# processingController.net
KiCad netlist of a schematic drawn in EAGLE
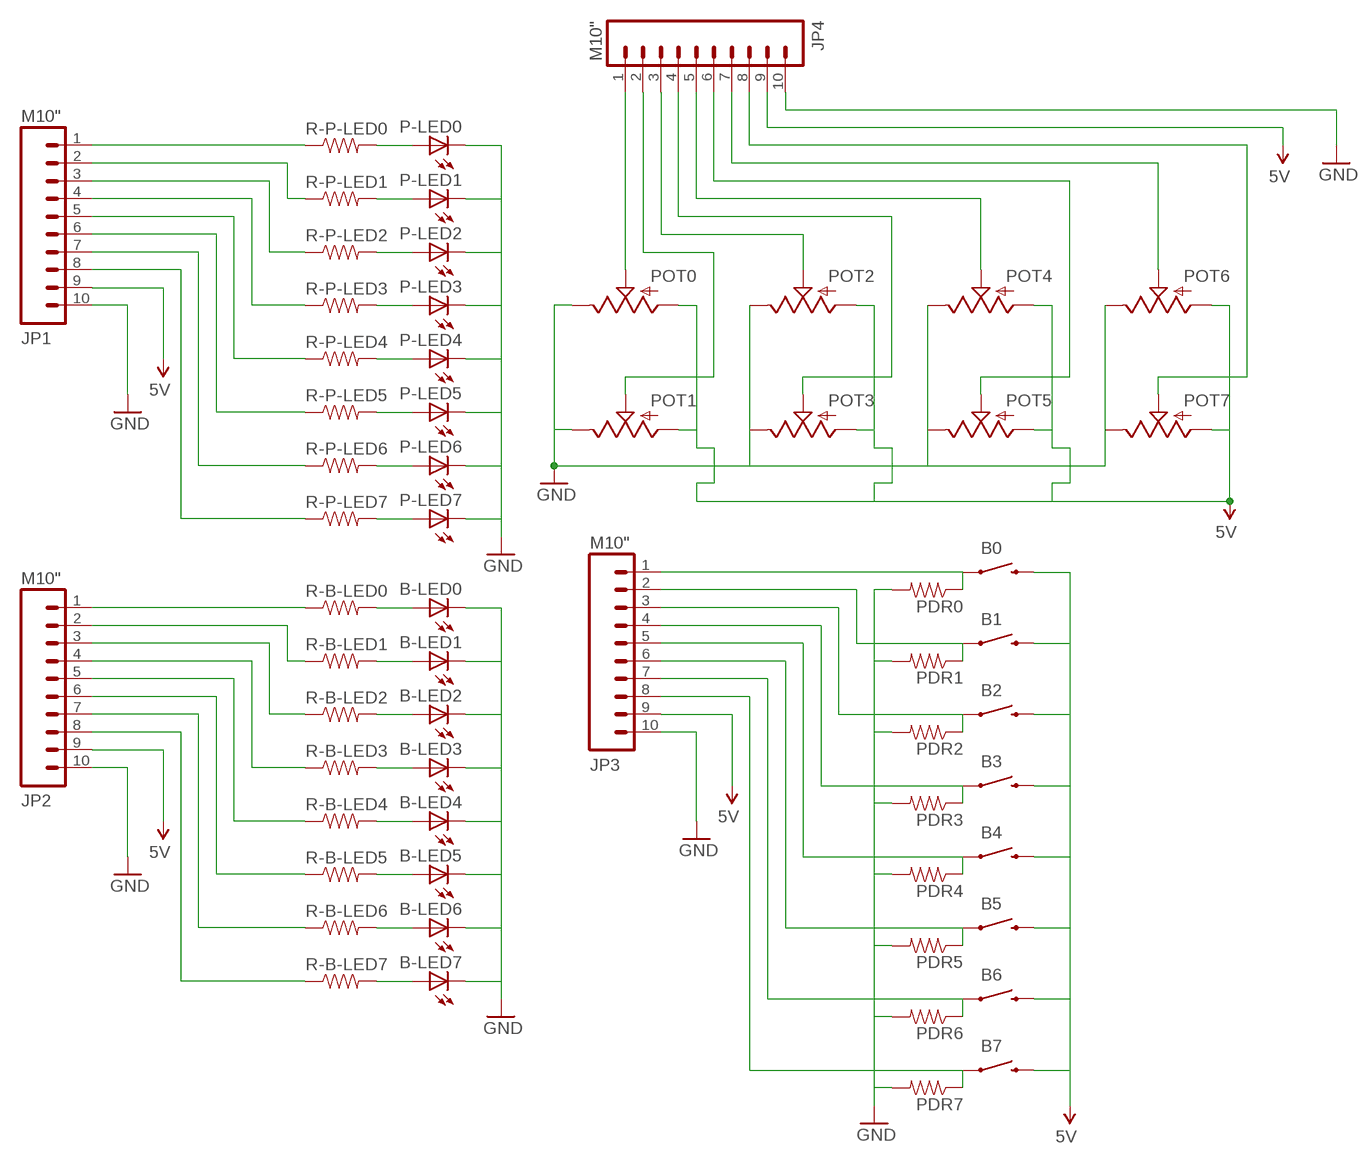
[diagram p0: schematic, sheet 1]

(export (version "E")
  (design (tool "Eeschema 10.0.6"))
  (components
    (comp (ref "B-LED0")
      (value "LED3MM")
      (footprint "eagle-import:LED3MM")
      (libsource (lib "eagle-import") (part "LED3MM"))
    )
    (comp (ref "B-LED1")
      (value "LED3MM")
      (footprint "eagle-import:LED3MM")
      (libsource (lib "eagle-import") (part "LED3MM"))
    )
    (comp (ref "B-LED2")
      (value "LED3MM")
      (footprint "eagle-import:LED3MM")
      (libsource (lib "eagle-import") (part "LED3MM"))
    )
    (comp (ref "B-LED3")
      (value "LED3MM")
      (footprint "eagle-import:LED3MM")
      (libsource (lib "eagle-import") (part "LED3MM"))
    )
    (comp (ref "B-LED4")
      (value "LED3MM")
      (footprint "eagle-import:LED3MM")
      (libsource (lib "eagle-import") (part "LED3MM"))
    )
    (comp (ref "B-LED5")
      (value "LED3MM")
      (footprint "eagle-import:LED3MM")
      (libsource (lib "eagle-import") (part "LED3MM"))
    )
    (comp (ref "B-LED6")
      (value "LED3MM")
      (footprint "eagle-import:LED3MM")
      (libsource (lib "eagle-import") (part "LED3MM"))
    )
    (comp (ref "B-LED7")
      (value "LED3MM")
      (footprint "eagle-import:LED3MM")
      (libsource (lib "eagle-import") (part "LED3MM"))
    )
    (comp (ref "B0")
      (value "SWITCH-MOMENTARY-212MM")
      (footprint "eagle-import:TACTILE-PTH-12MM")
      (libsource (lib "eagle-import") (part "SWITCH-MOMENTARY-212MM"))
    )
    (comp (ref "B1")
      (value "SWITCH-MOMENTARY-212MM")
      (footprint "eagle-import:TACTILE-PTH-12MM")
      (libsource (lib "eagle-import") (part "SWITCH-MOMENTARY-212MM"))
    )
    (comp (ref "B2")
      (value "SWITCH-MOMENTARY-212MM")
      (footprint "eagle-import:TACTILE-PTH-12MM")
      (libsource (lib "eagle-import") (part "SWITCH-MOMENTARY-212MM"))
    )
    (comp (ref "B3")
      (value "SWITCH-MOMENTARY-212MM")
      (footprint "eagle-import:TACTILE-PTH-12MM")
      (libsource (lib "eagle-import") (part "SWITCH-MOMENTARY-212MM"))
    )
    (comp (ref "B4")
      (value "SWITCH-MOMENTARY-212MM")
      (footprint "eagle-import:TACTILE-PTH-12MM")
      (libsource (lib "eagle-import") (part "SWITCH-MOMENTARY-212MM"))
    )
    (comp (ref "B5")
      (value "SWITCH-MOMENTARY-212MM")
      (footprint "eagle-import:TACTILE-PTH-12MM")
      (libsource (lib "eagle-import") (part "SWITCH-MOMENTARY-212MM"))
    )
    (comp (ref "B6")
      (value "SWITCH-MOMENTARY-212MM")
      (footprint "eagle-import:TACTILE-PTH-12MM")
      (libsource (lib "eagle-import") (part "SWITCH-MOMENTARY-212MM"))
    )
    (comp (ref "B7")
      (value "SWITCH-MOMENTARY-212MM")
      (footprint "eagle-import:TACTILE-PTH-12MM")
      (libsource (lib "eagle-import") (part "SWITCH-MOMENTARY-212MM"))
    )
    (comp (ref "JP1")
      (value "M10\"")
      (footprint "eagle-import:1X10")
      (libsource (lib "eagle-import") (part "M10{dblquote}"))
    )
    (comp (ref "JP2")
      (value "M10\"")
      (footprint "eagle-import:1X10")
      (libsource (lib "eagle-import") (part "M10{dblquote}"))
    )
    (comp (ref "JP3")
      (value "M10\"")
      (footprint "eagle-import:1X10")
      (libsource (lib "eagle-import") (part "M10{dblquote}"))
    )
    (comp (ref "JP4")
      (value "M10\"")
      (footprint "eagle-import:1X10")
      (libsource (lib "eagle-import") (part "M10{dblquote}"))
    )
    (comp (ref "P-LED0")
      (value "LED3MM")
      (footprint "eagle-import:LED3MM")
      (libsource (lib "eagle-import") (part "LED3MM"))
    )
    (comp (ref "P-LED1")
      (value "LED3MM")
      (footprint "eagle-import:LED3MM")
      (libsource (lib "eagle-import") (part "LED3MM"))
    )
    (comp (ref "P-LED2")
      (value "LED3MM")
      (footprint "eagle-import:LED3MM")
      (libsource (lib "eagle-import") (part "LED3MM"))
    )
    (comp (ref "P-LED3")
      (value "LED3MM")
      (footprint "eagle-import:LED3MM")
      (libsource (lib "eagle-import") (part "LED3MM"))
    )
    (comp (ref "P-LED4")
      (value "LED3MM")
      (footprint "eagle-import:LED3MM")
      (libsource (lib "eagle-import") (part "LED3MM"))
    )
    (comp (ref "P-LED5")
      (value "LED3MM")
      (footprint "eagle-import:LED3MM")
      (libsource (lib "eagle-import") (part "LED3MM"))
    )
    (comp (ref "P-LED6")
      (value "LED3MM")
      (footprint "eagle-import:LED3MM")
      (libsource (lib "eagle-import") (part "LED3MM"))
    )
    (comp (ref "P-LED7")
      (value "LED3MM")
      (footprint "eagle-import:LED3MM")
      (libsource (lib "eagle-import") (part "LED3MM"))
    )
    (comp (ref "PDR0")
      (value "RESISTOREZ")
      (footprint "eagle-import:AXIAL-0.3EZ")
      (libsource (lib "eagle-import") (part "RESISTOREZ"))
    )
    (comp (ref "PDR1")
      (value "RESISTOREZ")
      (footprint "eagle-import:AXIAL-0.3EZ")
      (libsource (lib "eagle-import") (part "RESISTOREZ"))
    )
    (comp (ref "PDR2")
      (value "RESISTOREZ")
      (footprint "eagle-import:AXIAL-0.3EZ")
      (libsource (lib "eagle-import") (part "RESISTOREZ"))
    )
    (comp (ref "PDR3")
      (value "RESISTOREZ")
      (footprint "eagle-import:AXIAL-0.3EZ")
      (libsource (lib "eagle-import") (part "RESISTOREZ"))
    )
    (comp (ref "PDR4")
      (value "RESISTOREZ")
      (footprint "eagle-import:AXIAL-0.3EZ")
      (libsource (lib "eagle-import") (part "RESISTOREZ"))
    )
    (comp (ref "PDR5")
      (value "RESISTOREZ")
      (footprint "eagle-import:AXIAL-0.3EZ")
      (libsource (lib "eagle-import") (part "RESISTOREZ"))
    )
    (comp (ref "PDR6")
      (value "RESISTOREZ")
      (footprint "eagle-import:AXIAL-0.3EZ")
      (libsource (lib "eagle-import") (part "RESISTOREZ"))
    )
    (comp (ref "PDR7")
      (value "RESISTOREZ")
      (footprint "eagle-import:AXIAL-0.3EZ")
      (libsource (lib "eagle-import") (part "RESISTOREZ"))
    )
    (comp (ref "POT0")
      (value "POT")
      (footprint "eagle-import:ALPS_POT")
      (libsource (lib "eagle-import") (part "POT"))
    )
    (comp (ref "POT1")
      (value "POT")
      (footprint "eagle-import:ALPS_POT")
      (libsource (lib "eagle-import") (part "POT"))
    )
    (comp (ref "POT2")
      (value "POT")
      (footprint "eagle-import:ALPS_POT")
      (libsource (lib "eagle-import") (part "POT"))
    )
    (comp (ref "POT3")
      (value "POT")
      (footprint "eagle-import:ALPS_POT")
      (libsource (lib "eagle-import") (part "POT"))
    )
    (comp (ref "POT4")
      (value "POT")
      (footprint "eagle-import:ALPS_POT")
      (libsource (lib "eagle-import") (part "POT"))
    )
    (comp (ref "POT5")
      (value "POT")
      (footprint "eagle-import:ALPS_POT")
      (libsource (lib "eagle-import") (part "POT"))
    )
    (comp (ref "POT6")
      (value "POT")
      (footprint "eagle-import:ALPS_POT")
      (libsource (lib "eagle-import") (part "POT"))
    )
    (comp (ref "POT7")
      (value "POT")
      (footprint "eagle-import:ALPS_POT")
      (libsource (lib "eagle-import") (part "POT"))
    )
    (comp (ref "R-B-LED0")
      (value "RESISTOREZ")
      (footprint "eagle-import:AXIAL-0.3EZ")
      (libsource (lib "eagle-import") (part "RESISTOREZ"))
    )
    (comp (ref "R-B-LED1")
      (value "RESISTOREZ")
      (footprint "eagle-import:AXIAL-0.3EZ")
      (libsource (lib "eagle-import") (part "RESISTOREZ"))
    )
    (comp (ref "R-B-LED2")
      (value "RESISTOREZ")
      (footprint "eagle-import:AXIAL-0.3EZ")
      (libsource (lib "eagle-import") (part "RESISTOREZ"))
    )
    (comp (ref "R-B-LED3")
      (value "RESISTOREZ")
      (footprint "eagle-import:AXIAL-0.3EZ")
      (libsource (lib "eagle-import") (part "RESISTOREZ"))
    )
    (comp (ref "R-B-LED4")
      (value "RESISTOREZ")
      (footprint "eagle-import:AXIAL-0.3EZ")
      (libsource (lib "eagle-import") (part "RESISTOREZ"))
    )
    (comp (ref "R-B-LED5")
      (value "RESISTOREZ")
      (footprint "eagle-import:AXIAL-0.3EZ")
      (libsource (lib "eagle-import") (part "RESISTOREZ"))
    )
    (comp (ref "R-B-LED6")
      (value "RESISTOREZ")
      (footprint "eagle-import:AXIAL-0.3EZ")
      (libsource (lib "eagle-import") (part "RESISTOREZ"))
    )
    (comp (ref "R-B-LED7")
      (value "RESISTOREZ")
      (footprint "eagle-import:AXIAL-0.3EZ")
      (libsource (lib "eagle-import") (part "RESISTOREZ"))
    )
    (comp (ref "R-P-LED0")
      (value "RESISTOREZ")
      (footprint "eagle-import:AXIAL-0.3EZ")
      (libsource (lib "eagle-import") (part "RESISTOREZ"))
    )
    (comp (ref "R-P-LED1")
      (value "RESISTOREZ")
      (footprint "eagle-import:AXIAL-0.3EZ")
      (libsource (lib "eagle-import") (part "RESISTOREZ"))
    )
    (comp (ref "R-P-LED2")
      (value "RESISTOREZ")
      (footprint "eagle-import:AXIAL-0.3EZ")
      (libsource (lib "eagle-import") (part "RESISTOREZ"))
    )
    (comp (ref "R-P-LED3")
      (value "RESISTOREZ")
      (footprint "eagle-import:AXIAL-0.3EZ")
      (libsource (lib "eagle-import") (part "RESISTOREZ"))
    )
    (comp (ref "R-P-LED4")
      (value "RESISTOREZ")
      (footprint "eagle-import:AXIAL-0.3EZ")
      (libsource (lib "eagle-import") (part "RESISTOREZ"))
    )
    (comp (ref "R-P-LED5")
      (value "RESISTOREZ")
      (footprint "eagle-import:AXIAL-0.3EZ")
      (libsource (lib "eagle-import") (part "RESISTOREZ"))
    )
    (comp (ref "R-P-LED6")
      (value "RESISTOREZ")
      (footprint "eagle-import:AXIAL-0.3EZ")
      (libsource (lib "eagle-import") (part "RESISTOREZ"))
    )
    (comp (ref "R-P-LED7")
      (value "RESISTOREZ")
      (footprint "eagle-import:AXIAL-0.3EZ")
      (libsource (lib "eagle-import") (part "RESISTOREZ"))
    )
  )
  (nets
    (net (code "1") (name "5V") (class "Default")
      (node (ref "B0") (pin "3") (pinfunction "2_3") (pintype "passive"))
      (node (ref "B1") (pin "3") (pinfunction "2_3") (pintype "passive"))
      (node (ref "B2") (pin "3") (pinfunction "2_3") (pintype "passive"))
      (node (ref "B3") (pin "3") (pinfunction "2_3") (pintype "passive"))
      (node (ref "B4") (pin "3") (pinfunction "2_3") (pintype "passive"))
      (node (ref "B5") (pin "3") (pinfunction "2_3") (pintype "passive"))
      (node (ref "B6") (pin "3") (pinfunction "2_3") (pintype "passive"))
      (node (ref "B7") (pin "3") (pinfunction "2_3") (pintype "passive"))
      (node (ref "JP1") (pin "9") (pinfunction "9_9") (pintype "passive"))
      (node (ref "JP2") (pin "9") (pinfunction "9_9") (pintype "passive"))
      (node (ref "JP3") (pin "9") (pinfunction "9_9") (pintype "passive"))
      (node (ref "JP4") (pin "9") (pinfunction "9_9") (pintype "passive"))
      (node (ref "POT0") (pin "P$3") (pinfunction "A_P$3") (pintype "passive"))
      (node (ref "POT1") (pin "P$3") (pinfunction "A_P$3") (pintype "passive"))
      (node (ref "POT2") (pin "P$3") (pinfunction "A_P$3") (pintype "passive"))
      (node (ref "POT3") (pin "P$3") (pinfunction "A_P$3") (pintype "passive"))
      (node (ref "POT4") (pin "P$3") (pinfunction "A_P$3") (pintype "passive"))
      (node (ref "POT5") (pin "P$3") (pinfunction "A_P$3") (pintype "passive"))
      (node (ref "POT6") (pin "P$3") (pinfunction "A_P$3") (pintype "passive"))
      (node (ref "POT7") (pin "P$3") (pinfunction "A_P$3") (pintype "passive"))
    )
    (net (code "2") (name "GND") (class "Default")
      (node (ref "B-LED0") (pin "K") (pinfunction "C_K") (pintype "passive"))
      (node (ref "B-LED1") (pin "K") (pinfunction "C_K") (pintype "passive"))
      (node (ref "B-LED2") (pin "K") (pinfunction "C_K") (pintype "passive"))
      (node (ref "B-LED3") (pin "K") (pinfunction "C_K") (pintype "passive"))
      (node (ref "B-LED4") (pin "K") (pinfunction "C_K") (pintype "passive"))
      (node (ref "B-LED5") (pin "K") (pinfunction "C_K") (pintype "passive"))
      (node (ref "B-LED6") (pin "K") (pinfunction "C_K") (pintype "passive"))
      (node (ref "B-LED7") (pin "K") (pinfunction "C_K") (pintype "passive"))
      (node (ref "JP1") (pin "10") (pinfunction "10_10") (pintype "passive"))
      (node (ref "JP2") (pin "10") (pinfunction "10_10") (pintype "passive"))
      (node (ref "JP3") (pin "10") (pinfunction "10_10") (pintype "passive"))
      (node (ref "JP4") (pin "10") (pinfunction "10_10") (pintype "passive"))
      (node (ref "P-LED0") (pin "K") (pinfunction "C_K") (pintype "passive"))
      (node (ref "P-LED1") (pin "K") (pinfunction "C_K") (pintype "passive"))
      (node (ref "P-LED2") (pin "K") (pinfunction "C_K") (pintype "passive"))
      (node (ref "P-LED3") (pin "K") (pinfunction "C_K") (pintype "passive"))
      (node (ref "P-LED4") (pin "K") (pinfunction "C_K") (pintype "passive"))
      (node (ref "P-LED5") (pin "K") (pinfunction "C_K") (pintype "passive"))
      (node (ref "P-LED6") (pin "K") (pinfunction "C_K") (pintype "passive"))
      (node (ref "P-LED7") (pin "K") (pinfunction "C_K") (pintype "passive"))
      (node (ref "PDR0") (pin "P$2") (pinfunction "2_P$2") (pintype "passive"))
      (node (ref "PDR1") (pin "P$2") (pinfunction "2_P$2") (pintype "passive"))
      (node (ref "PDR2") (pin "P$2") (pinfunction "2_P$2") (pintype "passive"))
      (node (ref "PDR3") (pin "P$2") (pinfunction "2_P$2") (pintype "passive"))
      (node (ref "PDR4") (pin "P$2") (pinfunction "2_P$2") (pintype "passive"))
      (node (ref "PDR5") (pin "P$2") (pinfunction "2_P$2") (pintype "passive"))
      (node (ref "PDR6") (pin "P$2") (pinfunction "2_P$2") (pintype "passive"))
      (node (ref "PDR7") (pin "P$2") (pinfunction "2_P$2") (pintype "passive"))
      (node (ref "POT0") (pin "P$1") (pinfunction "E_P$1") (pintype "passive"))
      (node (ref "POT1") (pin "P$1") (pinfunction "E_P$1") (pintype "passive"))
      (node (ref "POT2") (pin "P$1") (pinfunction "E_P$1") (pintype "passive"))
      (node (ref "POT3") (pin "P$1") (pinfunction "E_P$1") (pintype "passive"))
      (node (ref "POT4") (pin "P$1") (pinfunction "E_P$1") (pintype "passive"))
      (node (ref "POT5") (pin "P$1") (pinfunction "E_P$1") (pintype "passive"))
      (node (ref "POT6") (pin "P$1") (pinfunction "E_P$1") (pintype "passive"))
      (node (ref "POT7") (pin "P$1") (pinfunction "E_P$1") (pintype "passive"))
    )
    (net (code "3") (name "Net-(PDR0-1)") (class "Default")
      (node (ref "B0") (pin "1") (pinfunction "1_1") (pintype "passive"))
      (node (ref "JP3") (pin "1") (pinfunction "1_1") (pintype "passive"))
      (node (ref "PDR0") (pin "P$1") (pinfunction "1_P$1") (pintype "passive"))
    )
    (net (code "4") (name "Net-(PDR1-1)") (class "Default")
      (node (ref "B1") (pin "1") (pinfunction "1_1") (pintype "passive"))
      (node (ref "JP3") (pin "2") (pinfunction "2_2") (pintype "passive"))
      (node (ref "PDR1") (pin "P$1") (pinfunction "1_P$1") (pintype "passive"))
    )
    (net (code "5") (name "Net-(PDR2-1)") (class "Default")
      (node (ref "B2") (pin "1") (pinfunction "1_1") (pintype "passive"))
      (node (ref "JP3") (pin "3") (pinfunction "3_3") (pintype "passive"))
      (node (ref "PDR2") (pin "P$1") (pinfunction "1_P$1") (pintype "passive"))
    )
    (net (code "6") (name "Net-(PDR3-1)") (class "Default")
      (node (ref "B3") (pin "1") (pinfunction "1_1") (pintype "passive"))
      (node (ref "JP3") (pin "4") (pinfunction "4_4") (pintype "passive"))
      (node (ref "PDR3") (pin "P$1") (pinfunction "1_P$1") (pintype "passive"))
    )
    (net (code "7") (name "Net-(PDR4-1)") (class "Default")
      (node (ref "B4") (pin "1") (pinfunction "1_1") (pintype "passive"))
      (node (ref "JP3") (pin "5") (pinfunction "5_5") (pintype "passive"))
      (node (ref "PDR4") (pin "P$1") (pinfunction "1_P$1") (pintype "passive"))
    )
    (net (code "8") (name "Net-(PDR5-1)") (class "Default")
      (node (ref "B5") (pin "1") (pinfunction "1_1") (pintype "passive"))
      (node (ref "JP3") (pin "6") (pinfunction "6_6") (pintype "passive"))
      (node (ref "PDR5") (pin "P$1") (pinfunction "1_P$1") (pintype "passive"))
    )
    (net (code "9") (name "Net-(PDR6-1)") (class "Default")
      (node (ref "B6") (pin "1") (pinfunction "1_1") (pintype "passive"))
      (node (ref "JP3") (pin "7") (pinfunction "7_7") (pintype "passive"))
      (node (ref "PDR6") (pin "P$1") (pinfunction "1_P$1") (pintype "passive"))
    )
    (net (code "10") (name "Net-(PDR7-1)") (class "Default")
      (node (ref "B7") (pin "1") (pinfunction "1_1") (pintype "passive"))
      (node (ref "JP3") (pin "8") (pinfunction "8_8") (pintype "passive"))
      (node (ref "PDR7") (pin "P$1") (pinfunction "1_P$1") (pintype "passive"))
    )
    (net (code "11") (name "Net-(POT0-S)") (class "Default")
      (node (ref "JP4") (pin "1") (pinfunction "1_1") (pintype "passive"))
      (node (ref "POT0") (pin "P$2") (pinfunction "S_P$2") (pintype "passive"))
    )
    (net (code "12") (name "Net-(POT1-S)") (class "Default")
      (node (ref "JP4") (pin "2") (pinfunction "2_2") (pintype "passive"))
      (node (ref "POT1") (pin "P$2") (pinfunction "S_P$2") (pintype "passive"))
    )
    (net (code "13") (name "Net-(POT2-S)") (class "Default")
      (node (ref "JP4") (pin "3") (pinfunction "3_3") (pintype "passive"))
      (node (ref "POT2") (pin "P$2") (pinfunction "S_P$2") (pintype "passive"))
    )
    (net (code "14") (name "Net-(POT3-S)") (class "Default")
      (node (ref "JP4") (pin "4") (pinfunction "4_4") (pintype "passive"))
      (node (ref "POT3") (pin "P$2") (pinfunction "S_P$2") (pintype "passive"))
    )
    (net (code "15") (name "Net-(POT4-S)") (class "Default")
      (node (ref "JP4") (pin "5") (pinfunction "5_5") (pintype "passive"))
      (node (ref "POT4") (pin "P$2") (pinfunction "S_P$2") (pintype "passive"))
    )
    (net (code "16") (name "Net-(POT5-S)") (class "Default")
      (node (ref "JP4") (pin "6") (pinfunction "6_6") (pintype "passive"))
      (node (ref "POT5") (pin "P$2") (pinfunction "S_P$2") (pintype "passive"))
    )
    (net (code "17") (name "Net-(POT6-S)") (class "Default")
      (node (ref "JP4") (pin "7") (pinfunction "7_7") (pintype "passive"))
      (node (ref "POT6") (pin "P$2") (pinfunction "S_P$2") (pintype "passive"))
    )
    (net (code "18") (name "Net-(POT7-S)") (class "Default")
      (node (ref "JP4") (pin "8") (pinfunction "8_8") (pintype "passive"))
      (node (ref "POT7") (pin "P$2") (pinfunction "S_P$2") (pintype "passive"))
    )
    (net (code "19") (name "Net-(R-B-LED0-1)") (class "Default")
      (node (ref "JP2") (pin "1") (pinfunction "1_1") (pintype "passive"))
      (node (ref "R-B-LED0") (pin "P$1") (pinfunction "1_P$1") (pintype "passive"))
    )
    (net (code "20") (name "Net-(R-B-LED0-2)") (class "Default")
      (node (ref "B-LED0") (pin "A") (pinfunction "A_A") (pintype "passive"))
      (node (ref "R-B-LED0") (pin "P$2") (pinfunction "2_P$2") (pintype "passive"))
    )
    (net (code "21") (name "Net-(R-B-LED1-1)") (class "Default")
      (node (ref "JP2") (pin "2") (pinfunction "2_2") (pintype "passive"))
      (node (ref "R-B-LED1") (pin "P$1") (pinfunction "1_P$1") (pintype "passive"))
    )
    (net (code "22") (name "Net-(R-B-LED1-2)") (class "Default")
      (node (ref "B-LED1") (pin "A") (pinfunction "A_A") (pintype "passive"))
      (node (ref "R-B-LED1") (pin "P$2") (pinfunction "2_P$2") (pintype "passive"))
    )
    (net (code "23") (name "Net-(R-B-LED2-1)") (class "Default")
      (node (ref "JP2") (pin "3") (pinfunction "3_3") (pintype "passive"))
      (node (ref "R-B-LED2") (pin "P$1") (pinfunction "1_P$1") (pintype "passive"))
    )
    (net (code "24") (name "Net-(R-B-LED2-2)") (class "Default")
      (node (ref "B-LED2") (pin "A") (pinfunction "A_A") (pintype "passive"))
      (node (ref "R-B-LED2") (pin "P$2") (pinfunction "2_P$2") (pintype "passive"))
    )
    (net (code "25") (name "Net-(R-B-LED3-1)") (class "Default")
      (node (ref "JP2") (pin "4") (pinfunction "4_4") (pintype "passive"))
      (node (ref "R-B-LED3") (pin "P$1") (pinfunction "1_P$1") (pintype "passive"))
    )
    (net (code "26") (name "Net-(R-B-LED3-2)") (class "Default")
      (node (ref "B-LED3") (pin "A") (pinfunction "A_A") (pintype "passive"))
      (node (ref "R-B-LED3") (pin "P$2") (pinfunction "2_P$2") (pintype "passive"))
    )
    (net (code "27") (name "Net-(R-B-LED4-1)") (class "Default")
      (node (ref "JP2") (pin "5") (pinfunction "5_5") (pintype "passive"))
      (node (ref "R-B-LED4") (pin "P$1") (pinfunction "1_P$1") (pintype "passive"))
    )
    (net (code "28") (name "Net-(R-B-LED4-2)") (class "Default")
      (node (ref "B-LED4") (pin "A") (pinfunction "A_A") (pintype "passive"))
      (node (ref "R-B-LED4") (pin "P$2") (pinfunction "2_P$2") (pintype "passive"))
    )
    (net (code "29") (name "Net-(R-B-LED5-1)") (class "Default")
      (node (ref "JP2") (pin "6") (pinfunction "6_6") (pintype "passive"))
      (node (ref "R-B-LED5") (pin "P$1") (pinfunction "1_P$1") (pintype "passive"))
    )
    (net (code "30") (name "Net-(R-B-LED5-2)") (class "Default")
      (node (ref "B-LED5") (pin "A") (pinfunction "A_A") (pintype "passive"))
      (node (ref "R-B-LED5") (pin "P$2") (pinfunction "2_P$2") (pintype "passive"))
    )
    (net (code "31") (name "Net-(R-B-LED6-1)") (class "Default")
      (node (ref "JP2") (pin "7") (pinfunction "7_7") (pintype "passive"))
      (node (ref "R-B-LED6") (pin "P$1") (pinfunction "1_P$1") (pintype "passive"))
    )
    (net (code "32") (name "Net-(R-B-LED6-2)") (class "Default")
      (node (ref "B-LED6") (pin "A") (pinfunction "A_A") (pintype "passive"))
      (node (ref "R-B-LED6") (pin "P$2") (pinfunction "2_P$2") (pintype "passive"))
    )
    (net (code "33") (name "Net-(R-B-LED7-1)") (class "Default")
      (node (ref "JP2") (pin "8") (pinfunction "8_8") (pintype "passive"))
      (node (ref "R-B-LED7") (pin "P$1") (pinfunction "1_P$1") (pintype "passive"))
    )
    (net (code "34") (name "Net-(R-B-LED7-2)") (class "Default")
      (node (ref "B-LED7") (pin "A") (pinfunction "A_A") (pintype "passive"))
      (node (ref "R-B-LED7") (pin "P$2") (pinfunction "2_P$2") (pintype "passive"))
    )
    (net (code "35") (name "Net-(R-P-LED0-1)") (class "Default")
      (node (ref "JP1") (pin "1") (pinfunction "1_1") (pintype "passive"))
      (node (ref "R-P-LED0") (pin "P$1") (pinfunction "1_P$1") (pintype "passive"))
    )
    (net (code "36") (name "Net-(R-P-LED0-2)") (class "Default")
      (node (ref "P-LED0") (pin "A") (pinfunction "A_A") (pintype "passive"))
      (node (ref "R-P-LED0") (pin "P$2") (pinfunction "2_P$2") (pintype "passive"))
    )
    (net (code "37") (name "Net-(R-P-LED1-1)") (class "Default")
      (node (ref "JP1") (pin "2") (pinfunction "2_2") (pintype "passive"))
      (node (ref "R-P-LED1") (pin "P$1") (pinfunction "1_P$1") (pintype "passive"))
    )
    (net (code "38") (name "Net-(R-P-LED1-2)") (class "Default")
      (node (ref "P-LED1") (pin "A") (pinfunction "A_A") (pintype "passive"))
      (node (ref "R-P-LED1") (pin "P$2") (pinfunction "2_P$2") (pintype "passive"))
    )
    (net (code "39") (name "Net-(R-P-LED2-1)") (class "Default")
      (node (ref "JP1") (pin "3") (pinfunction "3_3") (pintype "passive"))
      (node (ref "R-P-LED2") (pin "P$1") (pinfunction "1_P$1") (pintype "passive"))
    )
    (net (code "40") (name "Net-(R-P-LED2-2)") (class "Default")
      (node (ref "P-LED2") (pin "A") (pinfunction "A_A") (pintype "passive"))
      (node (ref "R-P-LED2") (pin "P$2") (pinfunction "2_P$2") (pintype "passive"))
    )
    (net (code "41") (name "Net-(R-P-LED3-1)") (class "Default")
      (node (ref "JP1") (pin "4") (pinfunction "4_4") (pintype "passive"))
      (node (ref "R-P-LED3") (pin "P$1") (pinfunction "1_P$1") (pintype "passive"))
    )
    (net (code "42") (name "Net-(R-P-LED3-2)") (class "Default")
      (node (ref "P-LED3") (pin "A") (pinfunction "A_A") (pintype "passive"))
      (node (ref "R-P-LED3") (pin "P$2") (pinfunction "2_P$2") (pintype "passive"))
    )
    (net (code "43") (name "Net-(R-P-LED4-1)") (class "Default")
      (node (ref "JP1") (pin "5") (pinfunction "5_5") (pintype "passive"))
      (node (ref "R-P-LED4") (pin "P$1") (pinfunction "1_P$1") (pintype "passive"))
    )
    (net (code "44") (name "Net-(R-P-LED4-2)") (class "Default")
      (node (ref "P-LED4") (pin "A") (pinfunction "A_A") (pintype "passive"))
      (node (ref "R-P-LED4") (pin "P$2") (pinfunction "2_P$2") (pintype "passive"))
    )
    (net (code "45") (name "Net-(R-P-LED5-1)") (class "Default")
      (node (ref "JP1") (pin "6") (pinfunction "6_6") (pintype "passive"))
      (node (ref "R-P-LED5") (pin "P$1") (pinfunction "1_P$1") (pintype "passive"))
    )
    (net (code "46") (name "Net-(R-P-LED5-2)") (class "Default")
      (node (ref "P-LED5") (pin "A") (pinfunction "A_A") (pintype "passive"))
      (node (ref "R-P-LED5") (pin "P$2") (pinfunction "2_P$2") (pintype "passive"))
    )
    (net (code "47") (name "Net-(R-P-LED6-1)") (class "Default")
      (node (ref "JP1") (pin "7") (pinfunction "7_7") (pintype "passive"))
      (node (ref "R-P-LED6") (pin "P$1") (pinfunction "1_P$1") (pintype "passive"))
    )
    (net (code "48") (name "Net-(R-P-LED6-2)") (class "Default")
      (node (ref "P-LED6") (pin "A") (pinfunction "A_A") (pintype "passive"))
      (node (ref "R-P-LED6") (pin "P$2") (pinfunction "2_P$2") (pintype "passive"))
    )
    (net (code "49") (name "Net-(R-P-LED7-1)") (class "Default")
      (node (ref "JP1") (pin "8") (pinfunction "8_8") (pintype "passive"))
      (node (ref "R-P-LED7") (pin "P$1") (pinfunction "1_P$1") (pintype "passive"))
    )
    (net (code "50") (name "Net-(R-P-LED7-2)") (class "Default")
      (node (ref "P-LED7") (pin "A") (pinfunction "A_A") (pintype "passive"))
      (node (ref "R-P-LED7") (pin "P$2") (pinfunction "2_P$2") (pintype "passive"))
    )
  )
)
